# ALU_ADDER.net
KiCad netlist of a schematic drawn in Altium Designer
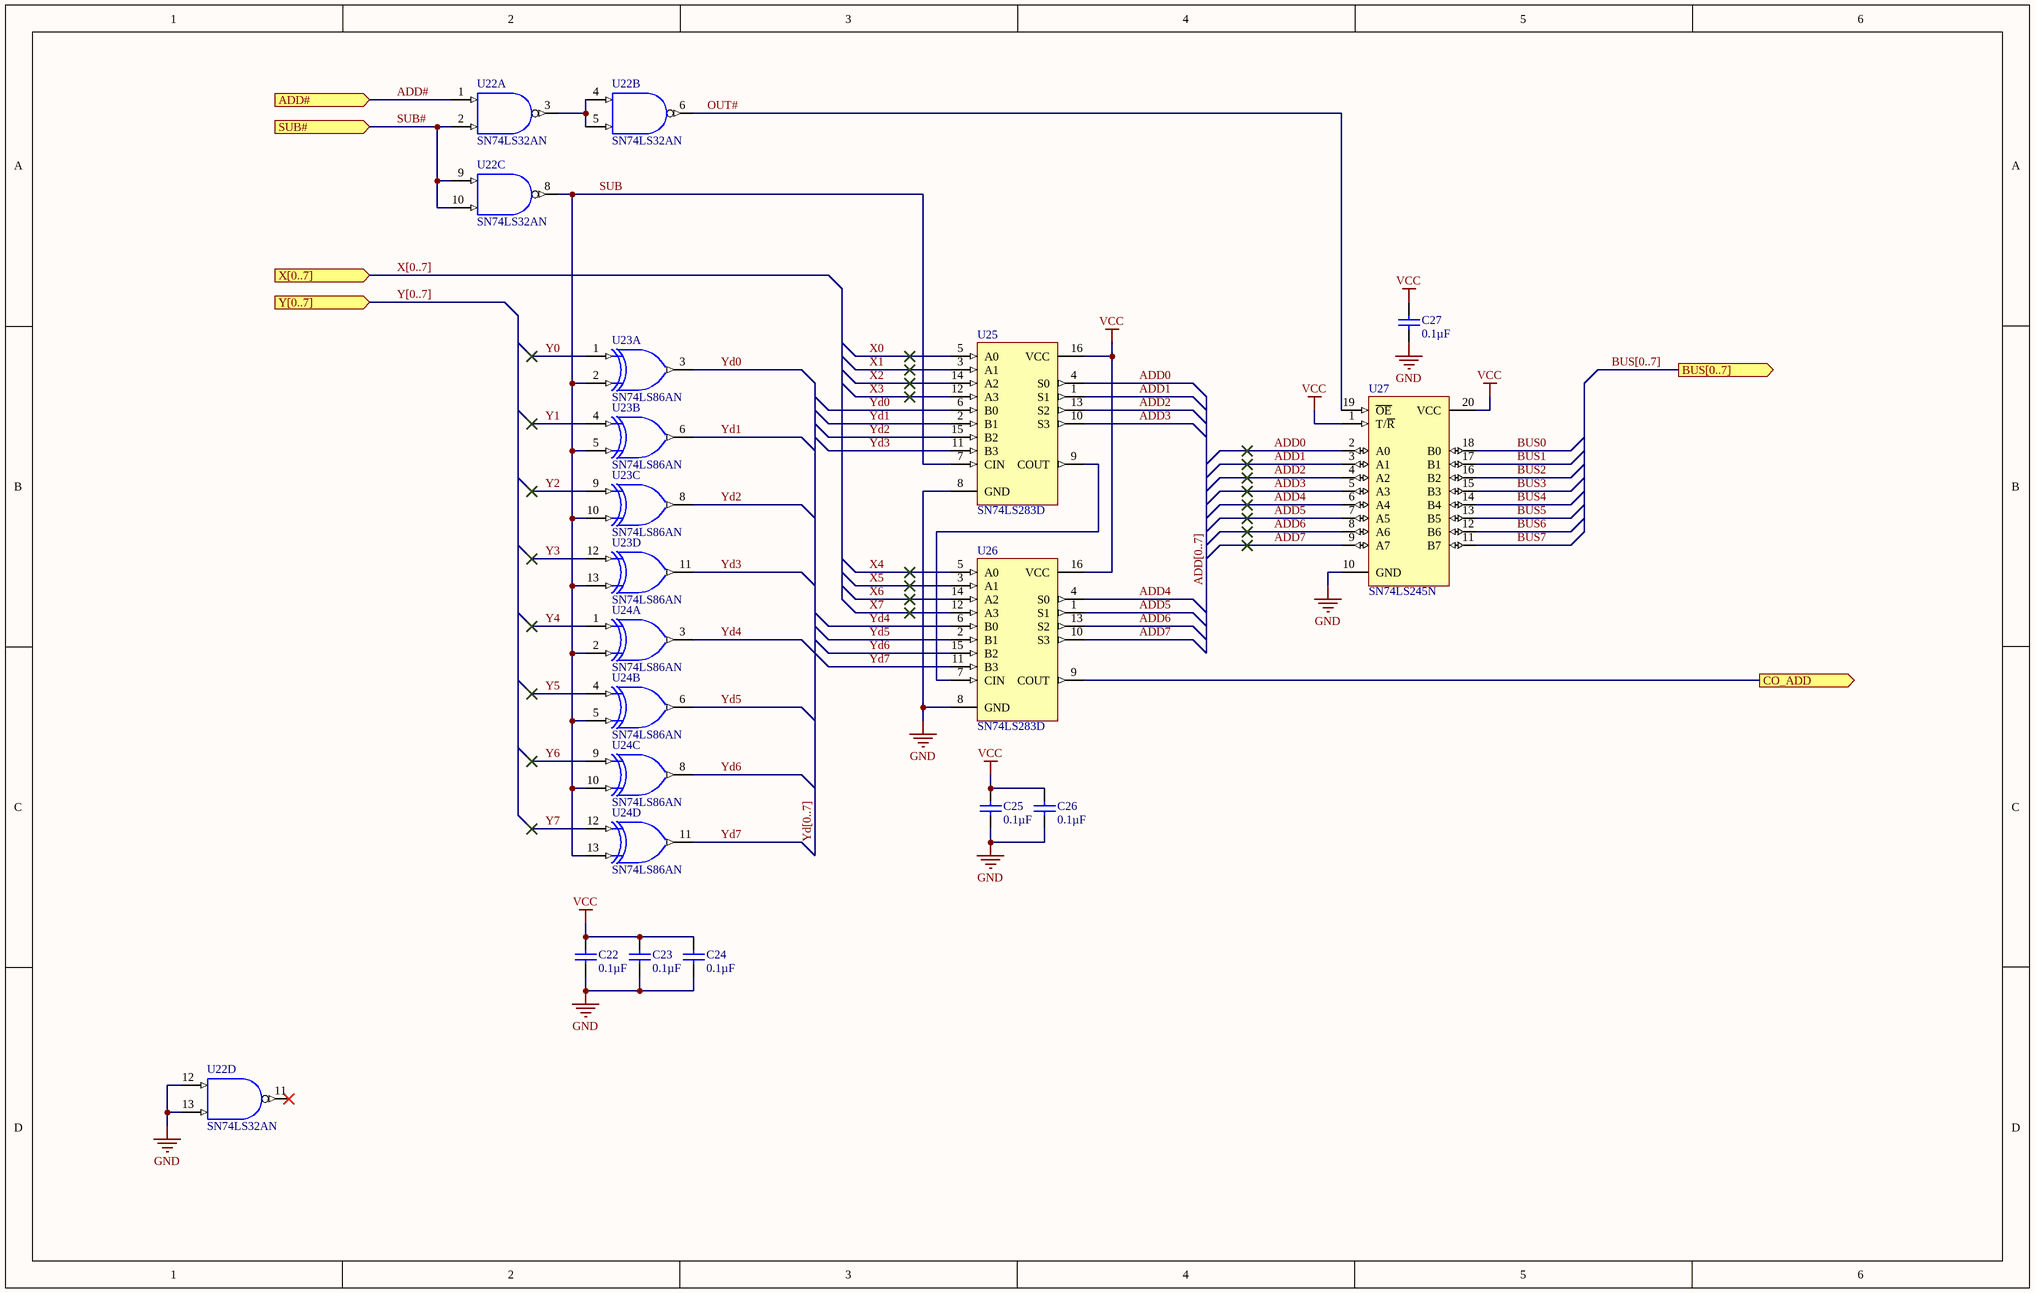
[diagram p0: ALU_ADDER.SchDoc]

(export (version "E")
  (design (tool "Eeschema 10.0.6"))
  (components
    (comp (ref "C22")
      (value "K104K15X7RF5TL2")
      (footprint "VISH-K104K15X7RF5TL2")
      (description "Ceramic Capacitor, 100 nF, +/- 10%, 50 V, -55 to 125 degC, 2-Pin THD, RoHS, Tape and Reel")
      (fields
        (field (name "MANUFACTURER") "Vishay")
        (field (name "TOLERANCE") "±10%")
        (field (name "CAPACITANCE") "0.1µF")
      )
      (libsource (lib "Altium Content Vault") (part "CAP-NP-2"))
    )
    (comp (ref "C23")
      (value "K104K15X7RF5TL2")
      (footprint "VISH-K104K15X7RF5TL2")
      (description "Ceramic Capacitor, 100 nF, +/- 10%, 50 V, -55 to 125 degC, 2-Pin THD, RoHS, Tape and Reel")
      (fields
        (field (name "MANUFACTURER") "Vishay")
        (field (name "TOLERANCE") "±10%")
        (field (name "CAPACITANCE") "0.1µF")
      )
      (libsource (lib "Altium Content Vault") (part "CAP-NP-2"))
    )
    (comp (ref "C24")
      (value "K104K15X7RF5TL2")
      (footprint "VISH-K104K15X7RF5TL2")
      (description "Ceramic Capacitor, 100 nF, +/- 10%, 50 V, -55 to 125 degC, 2-Pin THD, RoHS, Tape and Reel")
      (fields
        (field (name "MANUFACTURER") "Vishay")
        (field (name "TOLERANCE") "±10%")
        (field (name "CAPACITANCE") "0.1µF")
      )
      (libsource (lib "Altium Content Vault") (part "CAP-NP-2"))
    )
    (comp (ref "C25")
      (value "K104K15X7RF5TL2")
      (footprint "VISH-K104K15X7RF5TL2")
      (description "Ceramic Capacitor, 100 nF, +/- 10%, 50 V, -55 to 125 degC, 2-Pin THD, RoHS, Tape and Reel")
      (fields
        (field (name "MANUFACTURER") "Vishay")
        (field (name "TOLERANCE") "±10%")
        (field (name "CAPACITANCE") "0.1µF")
      )
      (libsource (lib "Altium Content Vault") (part "CAP-NP-2"))
    )
    (comp (ref "C26")
      (value "K104K15X7RF5TL2")
      (footprint "VISH-K104K15X7RF5TL2")
      (description "Ceramic Capacitor, 100 nF, +/- 10%, 50 V, -55 to 125 degC, 2-Pin THD, RoHS, Tape and Reel")
      (fields
        (field (name "MANUFACTURER") "Vishay")
        (field (name "TOLERANCE") "±10%")
        (field (name "CAPACITANCE") "0.1µF")
      )
      (libsource (lib "Altium Content Vault") (part "CAP-NP-2"))
    )
    (comp (ref "C27")
      (value "K104K15X7RF5TL2")
      (footprint "VISH-K104K15X7RF5TL2")
      (description "Ceramic Capacitor, 100 nF, +/- 10%, 50 V, -55 to 125 degC, 2-Pin THD, RoHS, Tape and Reel")
      (fields
        (field (name "MANUFACTURER") "Vishay")
        (field (name "TOLERANCE") "±10%")
        (field (name "CAPACITANCE") "0.1µF")
      )
      (libsource (lib "Altium Content Vault") (part "CAP-NP-2"))
    )
    (comp (ref "U22")
      (value "SN74LS32AN")
      (footprint "N014")
      (description "Quadruple 2-Input Positive-NAND Gate")
      (fields (field (name "PUBLISHER") "Altium Limited"))
      (libsource (lib "TI Logic Gate 2") (part "SN74LS00N"))
    )
    (comp (ref "U23")
      (value "SN74LS86AN")
      (footprint "N014")
      (description "Quadruple 2-Input Exclusive-OR Gate")
      (fields (field (name "PUBLISHER") "Altium Limited"))
      (libsource (lib "TI Logic Gate 2") (part "SN74LS86AN"))
    )
    (comp (ref "U24")
      (value "SN74LS86AN")
      (footprint "N014")
      (description "Quadruple 2-Input Exclusive-OR Gate")
      (fields (field (name "PUBLISHER") "Altium Limited"))
      (libsource (lib "TI Logic Gate 2") (part "SN74LS86AN"))
    )
    (comp (ref "U25")
      (value "SN74LS283D")
      (footprint "J016D")
      (description "4-Bit Binary Full Adder with Fast Carry")
      (fields (field (name "PUBLISHER") "Altium Limited"))
      (libsource (lib "TI Logic Arithmetic") (part "SN74LS283D"))
    )
    (comp (ref "U26")
      (value "SN74LS283D")
      (footprint "J016D")
      (description "4-Bit Binary Full Adder with Fast Carry")
      (fields (field (name "PUBLISHER") "Altium Limited"))
      (libsource (lib "TI Logic Arithmetic") (part "SN74LS283D"))
    )
    (comp (ref "U27")
      (value "SN74LS245N")
      (footprint "N020")
      (description "Octal Bus Transceiver with 3-State Outputs")
      (fields (field (name "PUBLISHER") "Altium Limited"))
      (libsource (lib "TI Interface 8-Bit Line Transceiver") (part "SN74LS245N"))
    )
  )
  (nets
    (net (code "1") (name "/ADD#") (class "Default")
      (node (ref "U22") (pin "1") (pinfunction "A_1") (pintype "input"))
    )
    (net (code "2") (name "/ADD0") (class "Default")
      (node (ref "U25") (pin "4") (pinfunction "S0_4") (pintype "output"))
      (node (ref "U27") (pin "2") (pinfunction "A0_2") (pintype "bidirectional"))
    )
    (net (code "3") (name "/ADD1") (class "Default")
      (node (ref "U25") (pin "1") (pinfunction "S1_1") (pintype "output"))
      (node (ref "U27") (pin "3") (pinfunction "A1_3") (pintype "bidirectional"))
    )
    (net (code "4") (name "/ADD2") (class "Default")
      (node (ref "U25") (pin "13") (pinfunction "S2_13") (pintype "output"))
      (node (ref "U27") (pin "4") (pinfunction "A2_4") (pintype "bidirectional"))
    )
    (net (code "5") (name "/ADD3") (class "Default")
      (node (ref "U25") (pin "10") (pinfunction "S3_10") (pintype "output"))
      (node (ref "U27") (pin "5") (pinfunction "A3_5") (pintype "bidirectional"))
    )
    (net (code "6") (name "/ADD4") (class "Default")
      (node (ref "U26") (pin "4") (pinfunction "S0_4") (pintype "output"))
      (node (ref "U27") (pin "6") (pinfunction "A4_6") (pintype "bidirectional"))
    )
    (net (code "7") (name "/ADD5") (class "Default")
      (node (ref "U26") (pin "1") (pinfunction "S1_1") (pintype "output"))
      (node (ref "U27") (pin "7") (pinfunction "A5_7") (pintype "bidirectional"))
    )
    (net (code "8") (name "/ADD6") (class "Default")
      (node (ref "U26") (pin "13") (pinfunction "S2_13") (pintype "output"))
      (node (ref "U27") (pin "8") (pinfunction "A6_8") (pintype "bidirectional"))
    )
    (net (code "9") (name "/ADD7") (class "Default")
      (node (ref "U26") (pin "10") (pinfunction "S3_10") (pintype "output"))
      (node (ref "U27") (pin "9") (pinfunction "A7_9") (pintype "bidirectional"))
    )
    (net (code "11") (name "/BUS0") (class "Default")
      (node (ref "U27") (pin "18") (pinfunction "B0_18") (pintype "bidirectional"))
    )
    (net (code "12") (name "/BUS1") (class "Default")
      (node (ref "U27") (pin "17") (pinfunction "B1_17") (pintype "bidirectional"))
    )
    (net (code "13") (name "/BUS2") (class "Default")
      (node (ref "U27") (pin "16") (pinfunction "B2_16") (pintype "bidirectional"))
    )
    (net (code "14") (name "/BUS3") (class "Default")
      (node (ref "U27") (pin "15") (pinfunction "B3_15") (pintype "bidirectional"))
    )
    (net (code "15") (name "/BUS4") (class "Default")
      (node (ref "U27") (pin "14") (pinfunction "B4_14") (pintype "bidirectional"))
    )
    (net (code "16") (name "/BUS5") (class "Default")
      (node (ref "U27") (pin "13") (pinfunction "B5_13") (pintype "bidirectional"))
    )
    (net (code "17") (name "/BUS6") (class "Default")
      (node (ref "U27") (pin "12") (pinfunction "B6_12") (pintype "bidirectional"))
    )
    (net (code "18") (name "/BUS7") (class "Default")
      (node (ref "U27") (pin "11") (pinfunction "B7_11") (pintype "bidirectional"))
    )
    (net (code "20") (name "/CO_ADD") (class "Default")
      (node (ref "U26") (pin "9") (pinfunction "COUT_9") (pintype "output"))
    )
    (net (code "21") (name "/OUT#") (class "Default")
      (node (ref "U22") (pin "6") (pinfunction "Y_6") (pintype "output"))
      (node (ref "U27") (pin "19") (pinfunction "~{OE}_19") (pintype "input"))
    )
    (net (code "22") (name "/SUB") (class "Default")
      (node (ref "U22") (pin "8") (pinfunction "Y_8") (pintype "output"))
      (node (ref "U23") (pin "10") (pinfunction "B_10") (pintype "input"))
      (node (ref "U23") (pin "13") (pinfunction "B_13") (pintype "input"))
      (node (ref "U23") (pin "2") (pinfunction "B_2") (pintype "input"))
      (node (ref "U23") (pin "5") (pinfunction "B_5") (pintype "input"))
      (node (ref "U24") (pin "10") (pinfunction "B_10") (pintype "input"))
      (node (ref "U24") (pin "13") (pinfunction "B_13") (pintype "input"))
      (node (ref "U24") (pin "2") (pinfunction "B_2") (pintype "input"))
      (node (ref "U24") (pin "5") (pinfunction "B_5") (pintype "input"))
      (node (ref "U25") (pin "7") (pinfunction "CIN_7") (pintype "input"))
    )
    (net (code "23") (name "/SUB#") (class "Default")
      (node (ref "U22") (pin "10") (pinfunction "B_10") (pintype "input"))
      (node (ref "U22") (pin "2") (pinfunction "B_2") (pintype "input"))
      (node (ref "U22") (pin "9") (pinfunction "A_9") (pintype "input"))
    )
    (net (code "24") (name "/X0") (class "Default")
      (node (ref "U25") (pin "5") (pinfunction "A0_5") (pintype "input"))
    )
    (net (code "25") (name "/X1") (class "Default")
      (node (ref "U25") (pin "3") (pinfunction "A1_3") (pintype "input"))
    )
    (net (code "26") (name "/X2") (class "Default")
      (node (ref "U25") (pin "14") (pinfunction "A2_14") (pintype "input"))
    )
    (net (code "27") (name "/X3") (class "Default")
      (node (ref "U25") (pin "12") (pinfunction "A3_12") (pintype "input"))
    )
    (net (code "28") (name "/X4") (class "Default")
      (node (ref "U26") (pin "5") (pinfunction "A0_5") (pintype "input"))
    )
    (net (code "29") (name "/X5") (class "Default")
      (node (ref "U26") (pin "3") (pinfunction "A1_3") (pintype "input"))
    )
    (net (code "30") (name "/X6") (class "Default")
      (node (ref "U26") (pin "14") (pinfunction "A2_14") (pintype "input"))
    )
    (net (code "31") (name "/X7") (class "Default")
      (node (ref "U26") (pin "12") (pinfunction "A3_12") (pintype "input"))
    )
    (net (code "33") (name "/Y0") (class "Default")
      (node (ref "U23") (pin "1") (pinfunction "A_1") (pintype "input+no_connect"))
    )
    (net (code "34") (name "/Y1") (class "Default")
      (node (ref "U23") (pin "4") (pinfunction "A_4") (pintype "input+no_connect"))
    )
    (net (code "35") (name "/Y2") (class "Default")
      (node (ref "U23") (pin "9") (pinfunction "A_9") (pintype "input+no_connect"))
    )
    (net (code "36") (name "/Y3") (class "Default")
      (node (ref "U23") (pin "12") (pinfunction "A_12") (pintype "input+no_connect"))
    )
    (net (code "37") (name "/Y4") (class "Default")
      (node (ref "U24") (pin "1") (pinfunction "A_1") (pintype "input+no_connect"))
    )
    (net (code "38") (name "/Y5") (class "Default")
      (node (ref "U24") (pin "4") (pinfunction "A_4") (pintype "input+no_connect"))
    )
    (net (code "39") (name "/Y6") (class "Default")
      (node (ref "U24") (pin "9") (pinfunction "A_9") (pintype "input+no_connect"))
    )
    (net (code "40") (name "/Y7") (class "Default")
      (node (ref "U24") (pin "12") (pinfunction "A_12") (pintype "input+no_connect"))
    )
    (net (code "42") (name "/Yd0") (class "Default")
      (node (ref "U23") (pin "3") (pinfunction "Y_3") (pintype "output"))
      (node (ref "U25") (pin "6") (pinfunction "B0_6") (pintype "input"))
    )
    (net (code "43") (name "/Yd1") (class "Default")
      (node (ref "U23") (pin "6") (pinfunction "Y_6") (pintype "output"))
      (node (ref "U25") (pin "2") (pinfunction "B1_2") (pintype "input"))
    )
    (net (code "44") (name "/Yd2") (class "Default")
      (node (ref "U23") (pin "8") (pinfunction "Y_8") (pintype "output"))
      (node (ref "U25") (pin "15") (pinfunction "B2_15") (pintype "input"))
    )
    (net (code "45") (name "/Yd3") (class "Default")
      (node (ref "U23") (pin "11") (pinfunction "Y_11") (pintype "output"))
      (node (ref "U25") (pin "11") (pinfunction "B3_11") (pintype "input"))
    )
    (net (code "46") (name "/Yd4") (class "Default")
      (node (ref "U24") (pin "3") (pinfunction "Y_3") (pintype "output"))
      (node (ref "U26") (pin "6") (pinfunction "B0_6") (pintype "input"))
    )
    (net (code "47") (name "/Yd5") (class "Default")
      (node (ref "U24") (pin "6") (pinfunction "Y_6") (pintype "output"))
      (node (ref "U26") (pin "2") (pinfunction "B1_2") (pintype "input"))
    )
    (net (code "48") (name "/Yd6") (class "Default")
      (node (ref "U24") (pin "8") (pinfunction "Y_8") (pintype "output"))
      (node (ref "U26") (pin "15") (pinfunction "B2_15") (pintype "input"))
    )
    (net (code "49") (name "/Yd7") (class "Default")
      (node (ref "U24") (pin "11") (pinfunction "Y_11") (pintype "output"))
      (node (ref "U26") (pin "11") (pinfunction "B3_11") (pintype "input"))
    )
    (net (code "51") (name "GND") (class "Default")
      (node (ref "C22") (pin "2") (pinfunction "2_2") (pintype "passive"))
      (node (ref "C23") (pin "2") (pinfunction "2_2") (pintype "passive"))
      (node (ref "C24") (pin "2") (pinfunction "2_2") (pintype "passive"))
      (node (ref "C25") (pin "2") (pinfunction "2_2") (pintype "passive"))
      (node (ref "C26") (pin "2") (pinfunction "2_2") (pintype "passive"))
      (node (ref "C27") (pin "2") (pinfunction "2_2") (pintype "passive"))
      (node (ref "U22") (pin "12") (pinfunction "A_12") (pintype "input"))
      (node (ref "U22") (pin "13") (pinfunction "B_13") (pintype "input"))
      (node (ref "U22") (pin "7") (pinfunction "GND_7") (pintype "power_in"))
      (node (ref "U23") (pin "7") (pinfunction "GND_7") (pintype "power_in"))
      (node (ref "U24") (pin "7") (pinfunction "GND_7") (pintype "power_in"))
      (node (ref "U25") (pin "8") (pinfunction "GND_8") (pintype "power_in"))
      (node (ref "U26") (pin "8") (pinfunction "GND_8") (pintype "power_in"))
      (node (ref "U27") (pin "10") (pinfunction "GND_10") (pintype "power_in"))
    )
    (net (code "52") (name "Net-(U22A-Y)") (class "Default")
      (node (ref "U22") (pin "3") (pinfunction "Y_3") (pintype "output"))
      (node (ref "U22") (pin "4") (pinfunction "A_4") (pintype "input"))
      (node (ref "U22") (pin "5") (pinfunction "B_5") (pintype "input"))
    )
    (net (code "53") (name "Net-(U25-COUT)") (class "Default")
      (node (ref "U25") (pin "9") (pinfunction "COUT_9") (pintype "output"))
      (node (ref "U26") (pin "7") (pinfunction "CIN_7") (pintype "input"))
    )
    (net (code "54") (name "VCC") (class "Default")
      (node (ref "C22") (pin "1") (pinfunction "1_1") (pintype "passive"))
      (node (ref "C23") (pin "1") (pinfunction "1_1") (pintype "passive"))
      (node (ref "C24") (pin "1") (pinfunction "1_1") (pintype "passive"))
      (node (ref "C25") (pin "1") (pinfunction "1_1") (pintype "passive"))
      (node (ref "C26") (pin "1") (pinfunction "1_1") (pintype "passive"))
      (node (ref "C27") (pin "1") (pinfunction "1_1") (pintype "passive"))
      (node (ref "U22") (pin "14") (pinfunction "VCC_14") (pintype "power_in"))
      (node (ref "U23") (pin "14") (pinfunction "VCC_14") (pintype "power_in"))
      (node (ref "U24") (pin "14") (pinfunction "VCC_14") (pintype "power_in"))
      (node (ref "U25") (pin "16") (pinfunction "VCC_16") (pintype "power_in"))
      (node (ref "U26") (pin "16") (pinfunction "VCC_16") (pintype "power_in"))
      (node (ref "U27") (pin "1") (pinfunction "T/~{R}_1") (pintype "input"))
      (node (ref "U27") (pin "20") (pinfunction "VCC_20") (pintype "power_in"))
    )
    (net (code "55") (name "unconnected-(U22D-Y-Pad11)") (class "Default")
      (node (ref "U22") (pin "11") (pinfunction "Y_11") (pintype "output+no_connect"))
    )
  )
)
